# Schematic.net
KiCad netlist of a schematic drawn in Altium Designer
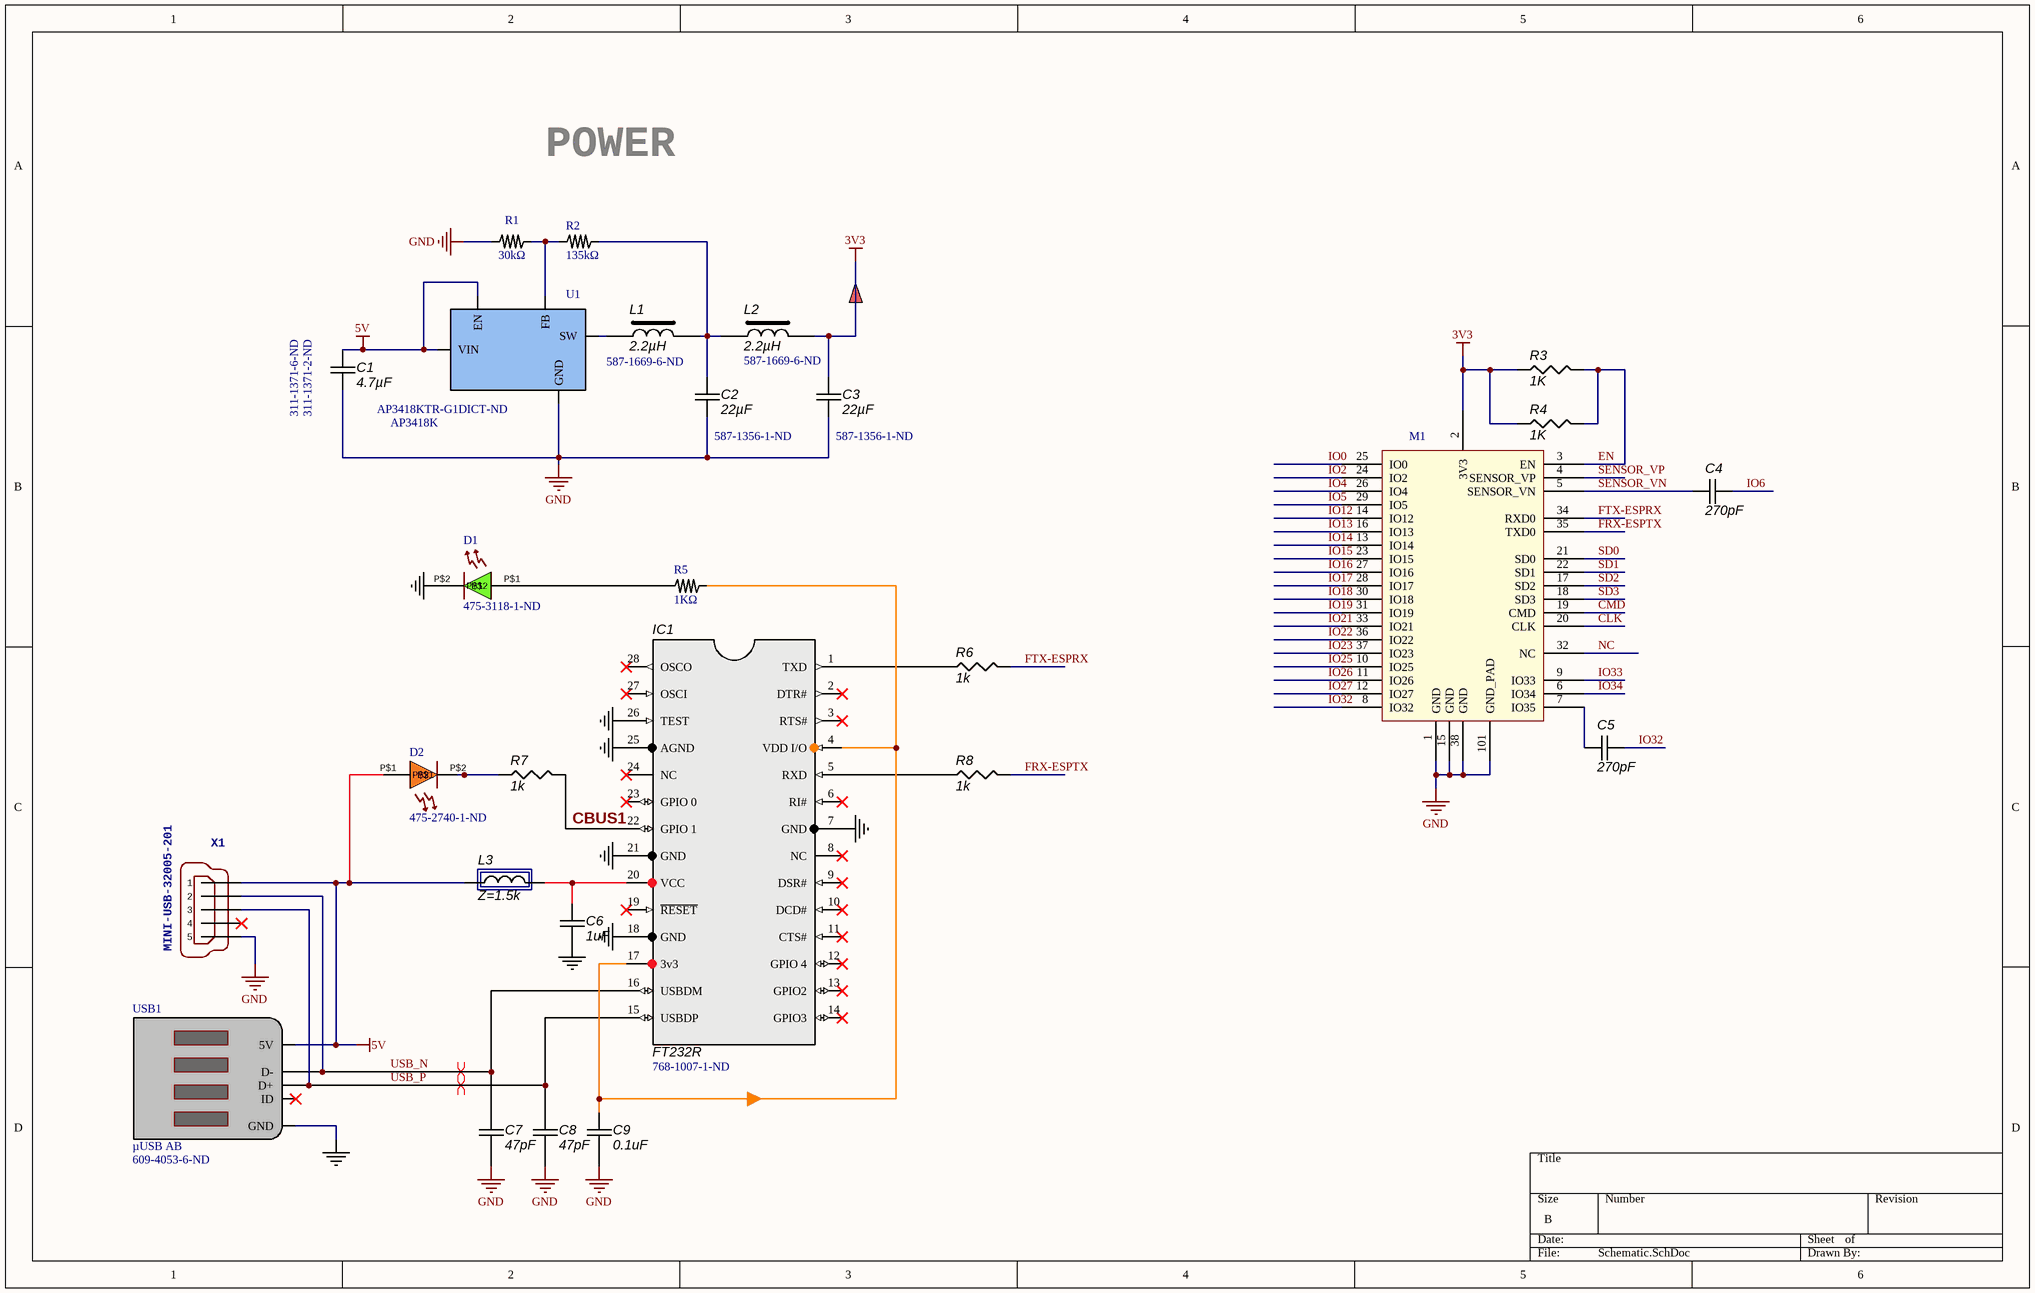
[diagram p0: Schematic.SchDoc]

(export (version "E")
  (design (tool "Eeschema 10.0.6"))
  (components
    (comp (ref "C1")
      (value "4.7µF")
      (footprint "0805NT")
      (description "Capacitor")
      (fields
        (field (name "VOLTAGE") "50v")
        (field (name "TOLERANCE") "5%")
        (field (name "SUPPLIER PART NUMBER 1") "311-1371-2-ND")
        (field (name "SUPPLIER PART NUMBER 2") "311-1371-6-ND")
      )
      (libsource (lib "Clau") (part "CAP"))
    )
    (comp (ref "C2")
      (value "22µF")
      (footprint "1206NT")
      (description "Capacitor")
      (fields
        (field (name "PART #") "ECJ-0EC1H101J")
        (field (name "VOLTAGE") "50v")
        (field (name "SUPPLIER PART NUMBER 1") "587-1356-1-ND")
      )
      (libsource (lib "Clau") (part "CAP"))
    )
    (comp (ref "C3")
      (value "22µF")
      (footprint "1206NT")
      (description "Capacitor")
      (fields
        (field (name "PART #") "ECJ-0EC1H101J")
        (field (name "VOLTAGE") "50v")
        (field (name "SUPPLIER PART NUMBER 1") "587-1356-1-ND")
      )
      (libsource (lib "Clau") (part "CAP"))
    )
    (comp (ref "C4")
      (value "270pF")
      (footprint "0603NT")
      (description "Capacitor")
      (fields (field (name "VOLTAGE") "50v") (field (name "TOLERANCE") "5%"))
      (libsource (lib "Clau") (part "CAP"))
    )
    (comp (ref "C5")
      (value "270pF")
      (footprint "0603NT")
      (description "Capacitor")
      (fields (field (name "VOLTAGE") "50v") (field (name "TOLERANCE") "5%"))
      (libsource (lib "Clau") (part "CAP"))
    )
    (comp (ref "C6")
      (value "1uF")
      (footprint "0402NT")
      (description "Capacitor")
      (fields (field (name "PART #") "C1608X5R1C105K") (field (name "VOLTAGE") "16v"))
      (libsource (lib "Clau") (part "CAP"))
    )
    (comp (ref "C7")
      (value "47pF")
      (footprint "0603NT")
      (description "Capacitor")
      (fields (field (name "PART #") "C1608C0G1H470J") (field (name "VOLTAGE") "50v"))
      (libsource (lib "Clau") (part "CAP"))
    )
    (comp (ref "C8")
      (value "47pF")
      (footprint "0603NT")
      (description "Capacitor")
      (fields (field (name "PART #") "C1608C0G1H470J") (field (name "VOLTAGE") "50v"))
      (libsource (lib "Clau") (part "CAP"))
    )
    (comp (ref "C9")
      (value "0.1uF")
      (footprint "0603NT")
      (description "Capacitor")
      (fields (field (name "PART #") "C1608C0G1H470J") (field (name "VOLTAGE") "50v"))
      (libsource (lib "Clau") (part "CAP"))
    )
    (comp (ref "D1")
      (value "SMT_LED")
      (footprint "0603(IN)LED")
      (fields (field (name "SUPPLIER PART NUMBER 1") "475-3118-1-ND"))
      (libsource (lib "SMT LED") (part "SMT_LED"))
    )
    (comp (ref "D2")
      (value "SMT_LED")
      (footprint "0603(IN)LED")
      (fields (field (name "SUPPLIER PART NUMBER 1") "475-2740-1-ND"))
      (libsource (lib "SMT LED") (part "SMT_LED"))
    )
    (comp (ref "IC1")
      (value "FT232R")
      (footprint "SSOP-28")
      (description "IC Logic Comm")
      (fields
        (field (name "PART #") "FT232RL")
        (field (name "VOLTAGE") "3.3v~5.25v")
        (field (name "SUPPLIER PART NUMBER 1") "768-1007-1-ND")
      )
      (libsource (lib "Clau") (part "FT232RL"))
    )
    (comp (ref "L1")
      (value "2.2µH")
      (footprint "Clau:IND-NR4018")
      (description "Inductance Power")
      (fields (field (name "SUPPLIER PART NUMBER 1") "587-1669-6-ND"))
      (libsource (lib "Clau") (part "IND-POWER"))
    )
    (comp (ref "L2")
      (value "2.2µH")
      (footprint "Clau:IND-NR4018")
      (description "Inductance Power")
      (fields (field (name "SUPPLIER PART NUMBER 1") "587-1669-6-ND"))
      (libsource (lib "Clau") (part "IND-POWER"))
    )
    (comp (ref "L3")
      (value "Z=1.5k")
      (footprint "0603NT")
      (description "Inductance Bead")
      (fields (field (name "PART #") "MMZ1608Y152B"))
      (libsource (lib "Clau") (part "IND_BEAD"))
    )
    (comp (ref "M1")
      (value "ESP32S_Module")
      (footprint "ESP32S")
      (description "Esp-32S")
      (libsource (lib "ESP32S") (part "ESP32S_Module"))
    )
    (comp (ref "R1") (value "30kΩ") (footprint "0402NT") (libsource (lib "Clau") (part "ResNico")))
    (comp (ref "R2") (value "135kΩ") (footprint "0402NT") (libsource (lib "Clau") (part "ResNico")))
    (comp (ref "R3")
      (value "1K")
      (footprint "0402NT")
      (description "Resistance")
      (libsource (lib "Clau") (part "RES"))
    )
    (comp (ref "R4")
      (value "1K")
      (footprint "0402NT")
      (description "Resistance")
      (libsource (lib "Clau") (part "RES"))
    )
    (comp (ref "R5") (value "1KΩ") (footprint "0402NT") (libsource (lib "Clau") (part "ResNico")))
    (comp (ref "R6")
      (value "1k")
      (footprint "0402NT")
      (description "Resistance")
      (fields (field (name "PART #") "ERJ-3GEYJ473V") (field (name "VOLTAGE") "50v"))
      (libsource (lib "Clau") (part "RES"))
    )
    (comp (ref "R7")
      (value "1k")
      (footprint "0402NT")
      (description "Resistance")
      (fields (field (name "PART #") "ERJ-3GEYJ271V") (field (name "VOLTAGE") "50v"))
      (libsource (lib "Clau") (part "RES"))
    )
    (comp (ref "R8")
      (value "1k")
      (footprint "0402NT")
      (description "Resistance")
      (fields (field (name "PART #") "ERJ-3GEYJ473V") (field (name "VOLTAGE") "50v"))
      (libsource (lib "Clau") (part "RES"))
    )
    (comp (ref "U1")
      (value "AP3418K")
      (footprint "AP3418K SOT25")
      (fields (field (name "SUPPLIER PART NUMBER 1") "AP3418KTR-G1DICT-ND"))
      (libsource (lib "Nico") (part "AP3418K"))
    )
    (comp (ref "USB1")
      (value "µUSB AB")
      (footprint "Micro USB A/B")
      (fields (field (name "SUPPLIER PART NUMBER 1") "609-4053-6-ND"))
      (libsource (lib "Nico") (part "Micro USB A/B"))
    )
    (comp (ref "X1")
      (value "MINI-USB-32005-201")
      (footprint "32005-201")
      (description "<b>MINI USB-B Conector</b><p>\nSource: www.cypressindustries.com")
      (libsource (lib "LoJackBikeCool4 USB_1") (part "MINI-USB-32005-201"))
    )
  )
  (nets
    (net (code "1") (name "/CBUS1") (class "Default")
      (node (ref "IC1") (pin "22") (pinfunction "GPIO_1_22") (pintype "bidirectional"))
      (node (ref "R7") (pin "2") (pinfunction "2_2") (pintype "passive"))
    )
    (net (code "2") (name "/CLK") (class "Default")
      (node (ref "M1") (pin "20") (pinfunction "CLK_20") (pintype "passive"))
    )
    (net (code "3") (name "/CMD") (class "Default")
      (node (ref "M1") (pin "19") (pinfunction "CMD_19") (pintype "passive"))
    )
    (net (code "4") (name "/EN") (class "Default")
      (node (ref "M1") (pin "3") (pinfunction "EN_3") (pintype "power_in"))
      (node (ref "R3") (pin "2") (pinfunction "2_2") (pintype "passive"))
      (node (ref "R4") (pin "2") (pinfunction "2_2") (pintype "passive"))
    )
    (net (code "5") (name "/FRX-ESPTX") (class "Default")
      (node (ref "M1") (pin "35") (pinfunction "TXD0_35") (pintype "passive"))
      (node (ref "R8") (pin "2") (pinfunction "2_2") (pintype "passive"))
    )
    (net (code "6") (name "/FTX-ESPRX") (class "Default")
      (node (ref "M1") (pin "34") (pinfunction "RXD0_34") (pintype "passive"))
      (node (ref "R6") (pin "2") (pinfunction "2_2") (pintype "passive"))
    )
    (net (code "7") (name "/IO0") (class "Default")
      (node (ref "M1") (pin "25") (pinfunction "IO0_25") (pintype "passive"))
    )
    (net (code "8") (name "/IO2") (class "Default")
      (node (ref "M1") (pin "24") (pinfunction "IO2_24") (pintype "passive"))
    )
    (net (code "9") (name "/IO4") (class "Default")
      (node (ref "M1") (pin "26") (pinfunction "IO4_26") (pintype "passive"))
    )
    (net (code "10") (name "/IO5") (class "Default")
      (node (ref "M1") (pin "29") (pinfunction "IO5_29") (pintype "passive"))
    )
    (net (code "11") (name "/IO6") (class "Default") (node (ref "C4") (pin "2") (pintype "passive")))
    (net (code "12") (name "/IO12") (class "Default")
      (node (ref "M1") (pin "14") (pinfunction "IO12_14") (pintype "passive"))
    )
    (net (code "13") (name "/IO13") (class "Default")
      (node (ref "M1") (pin "16") (pinfunction "IO13_16") (pintype "passive"))
    )
    (net (code "14") (name "/IO14") (class "Default")
      (node (ref "M1") (pin "13") (pinfunction "IO14_13") (pintype "passive"))
    )
    (net (code "15") (name "/IO15") (class "Default")
      (node (ref "M1") (pin "23") (pinfunction "IO15_23") (pintype "passive"))
    )
    (net (code "16") (name "/IO16") (class "Default")
      (node (ref "M1") (pin "27") (pinfunction "IO16_27") (pintype "passive"))
    )
    (net (code "17") (name "/IO17") (class "Default")
      (node (ref "M1") (pin "28") (pinfunction "IO17_28") (pintype "passive"))
    )
    (net (code "18") (name "/IO18") (class "Default")
      (node (ref "M1") (pin "30") (pinfunction "IO18_30") (pintype "passive"))
    )
    (net (code "19") (name "/IO19") (class "Default")
      (node (ref "M1") (pin "31") (pinfunction "IO19_31") (pintype "passive"))
    )
    (net (code "20") (name "/IO21") (class "Default")
      (node (ref "M1") (pin "33") (pinfunction "IO21_33") (pintype "passive"))
    )
    (net (code "21") (name "/IO22") (class "Default")
      (node (ref "M1") (pin "36") (pinfunction "IO22_36") (pintype "passive"))
    )
    (net (code "22") (name "/IO23") (class "Default")
      (node (ref "M1") (pin "37") (pinfunction "IO23_37") (pintype "passive"))
    )
    (net (code "23") (name "/IO25") (class "Default")
      (node (ref "M1") (pin "10") (pinfunction "IO25_10") (pintype "passive"))
    )
    (net (code "24") (name "/IO26") (class "Default")
      (node (ref "M1") (pin "11") (pinfunction "IO26_11") (pintype "passive"))
    )
    (net (code "25") (name "/IO27") (class "Default")
      (node (ref "M1") (pin "12") (pinfunction "IO27_12") (pintype "passive"))
    )
    (net (code "26") (name "/IO32") (class "Default")
      (node (ref "C5") (pin "1") (pintype "passive"))
      (node (ref "M1") (pin "8") (pinfunction "IO32_8") (pintype "passive"))
    )
    (net (code "27") (name "/IO33") (class "Default")
      (node (ref "M1") (pin "9") (pinfunction "IO33_9") (pintype "passive"))
    )
    (net (code "28") (name "/IO34") (class "Default")
      (node (ref "M1") (pin "6") (pinfunction "IO34_6") (pintype "passive"))
    )
    (net (code "29") (name "/NC") (class "Default")
      (node (ref "M1") (pin "32") (pinfunction "NC_32") (pintype "passive"))
    )
    (net (code "30") (name "/SD0") (class "Default")
      (node (ref "M1") (pin "21") (pinfunction "SD0_21") (pintype "passive"))
    )
    (net (code "31") (name "/SD1") (class "Default")
      (node (ref "M1") (pin "22") (pinfunction "SD1_22") (pintype "passive"))
    )
    (net (code "32") (name "/SD2") (class "Default")
      (node (ref "M1") (pin "17") (pinfunction "SD2_17") (pintype "passive"))
    )
    (net (code "33") (name "/SD3") (class "Default")
      (node (ref "M1") (pin "18") (pinfunction "SD3_18") (pintype "passive"))
    )
    (net (code "34") (name "/SENSOR_VN") (class "Default")
      (node (ref "C4") (pin "1") (pintype "passive"))
      (node (ref "M1") (pin "5") (pinfunction "SENSOR_VN_5") (pintype "passive"))
    )
    (net (code "35") (name "/SENSOR_VP") (class "Default")
      (node (ref "M1") (pin "4") (pinfunction "SENSOR_VP_4") (pintype "passive"))
    )
    (net (code "36") (name "/USB_N") (class "Default")
      (node (ref "C7") (pin "1") (pintype "passive"))
      (node (ref "IC1") (pin "16") (pinfunction "USBDM_16") (pintype "bidirectional"))
      (node (ref "USB1") (pin "2") (pinfunction "D-_2") (pintype "passive"))
      (node (ref "X1") (pin "2") (pinfunction "2_2") (pintype "passive"))
    )
    (net (code "37") (name "/USB_P") (class "Default")
      (node (ref "C8") (pin "1") (pintype "passive"))
      (node (ref "IC1") (pin "15") (pinfunction "USBDP_15") (pintype "bidirectional"))
      (node (ref "USB1") (pin "3") (pinfunction "D+_3") (pintype "passive"))
      (node (ref "X1") (pin "3") (pinfunction "3_3") (pintype "passive"))
    )
    (net (code "38") (name "3V3") (class "Default")
      (node (ref "C3") (pin "1") (pintype "passive"))
      (node (ref "L2") (pin "2") (pinfunction "2_2") (pintype "passive"))
      (node (ref "M1") (pin "2") (pinfunction "3V3_2") (pintype "power_in"))
      (node (ref "R3") (pin "1") (pinfunction "1_1") (pintype "passive"))
      (node (ref "R4") (pin "1") (pinfunction "1_1") (pintype "passive"))
    )
    (net (code "39") (name "5V") (class "Default")
      (node (ref "C1") (pin "2") (pintype "passive"))
      (node (ref "D2") (pin "P$1") (pinfunction "P$1_P$1") (pintype "passive"))
      (node (ref "L3") (pin "1") (pinfunction "1_1") (pintype "passive"))
      (node (ref "U1") (pin "1") (pinfunction "EN_1") (pintype "passive"))
      (node (ref "U1") (pin "4") (pinfunction "VIN_4") (pintype "passive"))
      (node (ref "USB1") (pin "1") (pinfunction "5V_1") (pintype "passive"))
      (node (ref "X1") (pin "1") (pinfunction "1_1") (pintype "passive"))
    )
    (net (code "40") (name "GND") (class "Default")
      (node (ref "C1") (pin "1") (pintype "passive"))
      (node (ref "C2") (pin "2") (pintype "passive"))
      (node (ref "C3") (pin "2") (pintype "passive"))
      (node (ref "C6") (pin "2") (pintype "passive"))
      (node (ref "C7") (pin "2") (pintype "passive"))
      (node (ref "C8") (pin "2") (pintype "passive"))
      (node (ref "C9") (pin "2") (pintype "passive"))
      (node (ref "D1") (pin "P$2") (pinfunction "P$2_P$2") (pintype "passive"))
      (node (ref "IC1") (pin "18") (pinfunction "GND_18") (pintype "passive"))
      (node (ref "IC1") (pin "21") (pinfunction "GND_21") (pintype "power_in"))
      (node (ref "IC1") (pin "25") (pinfunction "AGND_25") (pintype "passive"))
      (node (ref "IC1") (pin "26") (pinfunction "TEST_26") (pintype "input"))
      (node (ref "IC1") (pin "7") (pinfunction "GND_7") (pintype "passive"))
      (node (ref "M1") (pin "1") (pinfunction "GND_1") (pintype "power_in"))
      (node (ref "M1") (pin "101") (pinfunction "GND_PAD_101") (pintype "power_in"))
      (node (ref "M1") (pin "15") (pinfunction "GND_15") (pintype "power_in"))
      (node (ref "M1") (pin "38") (pinfunction "GND_38") (pintype "power_in"))
      (node (ref "R1") (pin "1") (pinfunction "1_1") (pintype "passive"))
      (node (ref "U1") (pin "2") (pinfunction "GND_2") (pintype "passive"))
      (node (ref "USB1") (pin "5") (pinfunction "GND_5") (pintype "passive"))
      (node (ref "X1") (pin "5") (pinfunction "5_5") (pintype "passive"))
    )
    (net (code "41") (name "Net-(C2-Pad1)") (class "Default")
      (node (ref "C2") (pin "1") (pintype "passive"))
      (node (ref "L1") (pin "2") (pinfunction "2_2") (pintype "passive"))
      (node (ref "L2") (pin "1") (pinfunction "1_1") (pintype "passive"))
      (node (ref "R2") (pin "2") (pinfunction "2_2") (pintype "passive"))
    )
    (net (code "42") (name "Net-(D1-PadP$1)") (class "Default")
      (node (ref "D1") (pin "P$1") (pinfunction "P$1_P$1") (pintype "passive"))
      (node (ref "R5") (pin "1") (pinfunction "1_1") (pintype "passive"))
    )
    (net (code "43") (name "Net-(D2-PadP$2)") (class "Default")
      (node (ref "D2") (pin "P$2") (pinfunction "P$2_P$2") (pintype "passive"))
      (node (ref "R7") (pin "1") (pinfunction "1_1") (pintype "passive"))
    )
    (net (code "44") (name "Net-(IC1-3v3)") (class "Default")
      (node (ref "C9") (pin "1") (pintype "passive"))
      (node (ref "IC1") (pin "17") (pinfunction "3v3_17") (pintype "output"))
      (node (ref "IC1") (pin "4") (pinfunction "VDD_I/O_4") (pintype "input"))
      (node (ref "R5") (pin "2") (pinfunction "2_2") (pintype "passive"))
    )
    (net (code "45") (name "Net-(IC1-RXD)") (class "Default")
      (node (ref "IC1") (pin "5") (pinfunction "RXD_5") (pintype "input"))
      (node (ref "R8") (pin "1") (pinfunction "1_1") (pintype "passive"))
    )
    (net (code "46") (name "Net-(IC1-TXD)") (class "Default")
      (node (ref "IC1") (pin "1") (pinfunction "TXD_1") (pintype "output"))
      (node (ref "R6") (pin "1") (pinfunction "1_1") (pintype "passive"))
    )
    (net (code "47") (name "Net-(IC1-VCC)") (class "Default")
      (node (ref "C6") (pin "1") (pintype "passive"))
      (node (ref "IC1") (pin "20") (pinfunction "VCC_20") (pintype "power_in"))
      (node (ref "L3") (pin "2") (pinfunction "2_2") (pintype "passive"))
    )
    (net (code "48") (name "Net-(M1-IO35)") (class "Default")
      (node (ref "C5") (pin "2") (pintype "passive"))
      (node (ref "M1") (pin "7") (pinfunction "IO35_7") (pintype "passive"))
    )
    (net (code "49") (name "Net-(U1-FB)") (class "Default")
      (node (ref "R1") (pin "2") (pinfunction "2_2") (pintype "passive"))
      (node (ref "R2") (pin "1") (pinfunction "1_1") (pintype "passive"))
      (node (ref "U1") (pin "5") (pinfunction "FB_5") (pintype "passive"))
    )
    (net (code "50") (name "Net-(U1-SW)") (class "Default")
      (node (ref "L1") (pin "1") (pinfunction "1_1") (pintype "passive"))
      (node (ref "U1") (pin "3") (pinfunction "SW_3") (pintype "passive"))
    )
    (net (code "51") (name "unconnected-(IC1-CTS#-Pad11)") (class "Default")
      (node (ref "IC1") (pin "11") (pinfunction "CTS#_11") (pintype "input+no_connect"))
    )
    (net (code "52") (name "unconnected-(IC1-DCD#-Pad10)") (class "Default")
      (node (ref "IC1") (pin "10") (pinfunction "DCD#_10") (pintype "input+no_connect"))
    )
    (net (code "53") (name "unconnected-(IC1-DSR#-Pad9)") (class "Default")
      (node (ref "IC1") (pin "9") (pinfunction "DSR#_9") (pintype "input+no_connect"))
    )
    (net (code "54") (name "unconnected-(IC1-DTR#-Pad2)") (class "Default")
      (node (ref "IC1") (pin "2") (pinfunction "DTR#_2") (pintype "output+no_connect"))
    )
    (net (code "55") (name "unconnected-(IC1-GPIO2-Pad13)") (class "Default")
      (node (ref "IC1") (pin "13") (pinfunction "GPIO2_13") (pintype "bidirectional+no_connect"))
    )
    (net (code "56") (name "unconnected-(IC1-GPIO3-Pad14)") (class "Default")
      (node (ref "IC1") (pin "14") (pinfunction "GPIO3_14") (pintype "bidirectional+no_connect"))
    )
    (net (code "57") (name "unconnected-(IC1-GPIO_0-Pad23)") (class "Default")
      (node (ref "IC1") (pin "23") (pinfunction "GPIO_0_23") (pintype "bidirectional+no_connect"))
    )
    (net (code "58") (name "unconnected-(IC1-GPIO_4-Pad12)") (class "Default")
      (node (ref "IC1") (pin "12") (pinfunction "GPIO_4_12") (pintype "bidirectional+no_connect"))
    )
    (net (code "59") (name "unconnected-(IC1-NC-Pad8)") (class "Default")
      (node (ref "IC1") (pin "8") (pinfunction "NC_8") (pintype "passive+no_connect"))
    )
    (net (code "60") (name "unconnected-(IC1-NC-Pad24)") (class "Default")
      (node (ref "IC1") (pin "24") (pinfunction "NC_24") (pintype "passive+no_connect"))
    )
    (net (code "61") (name "unconnected-(IC1-OSCI-Pad27)") (class "Default")
      (node (ref "IC1") (pin "27") (pinfunction "OSCI_27") (pintype "input+no_connect"))
    )
    (net (code "62") (name "unconnected-(IC1-OSCO-Pad28)") (class "Default")
      (node (ref "IC1") (pin "28") (pinfunction "OSCO_28") (pintype "output+no_connect"))
    )
    (net (code "63") (name "unconnected-(IC1-RI#-Pad6)") (class "Default")
      (node (ref "IC1") (pin "6") (pinfunction "RI#_6") (pintype "input+no_connect"))
    )
    (net (code "64") (name "unconnected-(IC1-RTS#-Pad3)") (class "Default")
      (node (ref "IC1") (pin "3") (pinfunction "RTS#_3") (pintype "output+no_connect"))
    )
    (net (code "65") (name "unconnected-(IC1-~{RESET}-Pad19)") (class "Default")
      (node (ref "IC1") (pin "19") (pinfunction "~{RESET}_19") (pintype "input+no_connect"))
    )
    (net (code "66") (name "unconnected-(USB1-ID-Pad4)") (class "Default")
      (node (ref "USB1") (pin "4") (pinfunction "ID_4") (pintype "passive+no_connect"))
    )
    (net (code "67") (name "unconnected-(X1-Pad4)") (class "Default")
      (node (ref "X1") (pin "4") (pinfunction "4_4") (pintype "passive+no_connect"))
    )
  )
)
